# Three_GPS_schematic.net
KiCad netlist of a schematic drawn in EAGLE
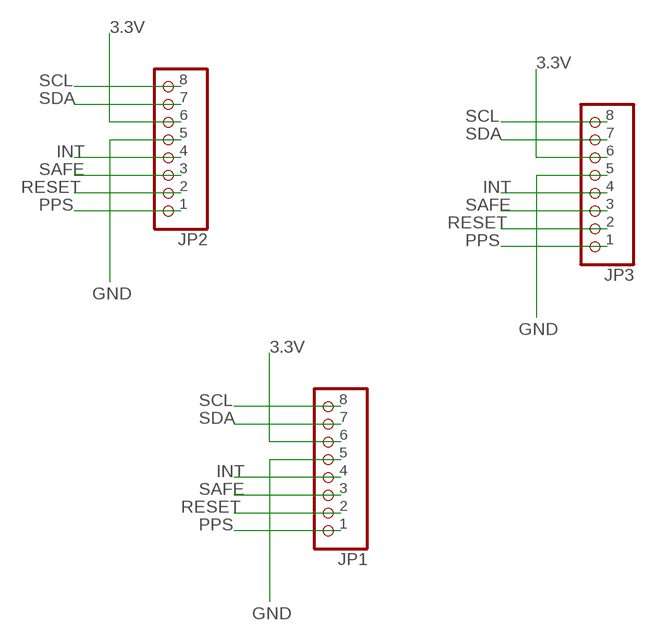
[diagram p0: schematic, sheet 1]

(export (version "E")
  (design (tool "Eeschema 10.0.6"))
  (components
    (comp (ref "JP1")
      (value "PINHD-1X8")
      (footprint "eagle-import:1X08")
      (libsource (lib "eagle-import") (part "PINHD-1X8"))
    )
    (comp (ref "JP2")
      (value "PINHD-1X8")
      (footprint "eagle-import:1X08")
      (libsource (lib "eagle-import") (part "PINHD-1X8"))
    )
    (comp (ref "JP3")
      (value "PINHD-1X8")
      (footprint "eagle-import:1X08")
      (libsource (lib "eagle-import") (part "PINHD-1X8"))
    )
  )
  (nets
    (net (code "1") (name "/3.3V") (class "Default")
      (node (ref "JP1") (pin "6") (pinfunction "6_6") (pintype "passive"))
      (node (ref "JP2") (pin "6") (pinfunction "6_6") (pintype "passive"))
      (node (ref "JP3") (pin "6") (pinfunction "6_6") (pintype "passive"))
    )
    (net (code "2") (name "/GND") (class "Default")
      (node (ref "JP1") (pin "5") (pinfunction "5_5") (pintype "passive"))
      (node (ref "JP2") (pin "5") (pinfunction "5_5") (pintype "passive"))
      (node (ref "JP3") (pin "5") (pinfunction "5_5") (pintype "passive"))
    )
    (net (code "3") (name "/INT") (class "Default")
      (node (ref "JP1") (pin "4") (pinfunction "4_4") (pintype "passive"))
      (node (ref "JP2") (pin "4") (pinfunction "4_4") (pintype "passive"))
      (node (ref "JP3") (pin "4") (pinfunction "4_4") (pintype "passive"))
    )
    (net (code "4") (name "/PPS") (class "Default")
      (node (ref "JP1") (pin "1") (pinfunction "1_1") (pintype "passive"))
      (node (ref "JP2") (pin "1") (pinfunction "1_1") (pintype "passive"))
      (node (ref "JP3") (pin "1") (pinfunction "1_1") (pintype "passive"))
    )
    (net (code "5") (name "/RESET") (class "Default")
      (node (ref "JP1") (pin "2") (pinfunction "2_2") (pintype "passive"))
      (node (ref "JP2") (pin "2") (pinfunction "2_2") (pintype "passive"))
      (node (ref "JP3") (pin "2") (pinfunction "2_2") (pintype "passive"))
    )
    (net (code "6") (name "/SAFE") (class "Default")
      (node (ref "JP1") (pin "3") (pinfunction "3_3") (pintype "passive"))
      (node (ref "JP2") (pin "3") (pinfunction "3_3") (pintype "passive"))
      (node (ref "JP3") (pin "3") (pinfunction "3_3") (pintype "passive"))
    )
    (net (code "7") (name "/SCL") (class "Default")
      (node (ref "JP1") (pin "8") (pinfunction "8_8") (pintype "passive"))
      (node (ref "JP2") (pin "8") (pinfunction "8_8") (pintype "passive"))
      (node (ref "JP3") (pin "8") (pinfunction "8_8") (pintype "passive"))
    )
    (net (code "8") (name "/SDA") (class "Default")
      (node (ref "JP1") (pin "7") (pinfunction "7_7") (pintype "passive"))
      (node (ref "JP2") (pin "7") (pinfunction "7_7") (pintype "passive"))
      (node (ref "JP3") (pin "7") (pinfunction "7_7") (pintype "passive"))
    )
  )
)
